# CPLD.net
KiCad netlist of a schematic drawn in Altium Designer
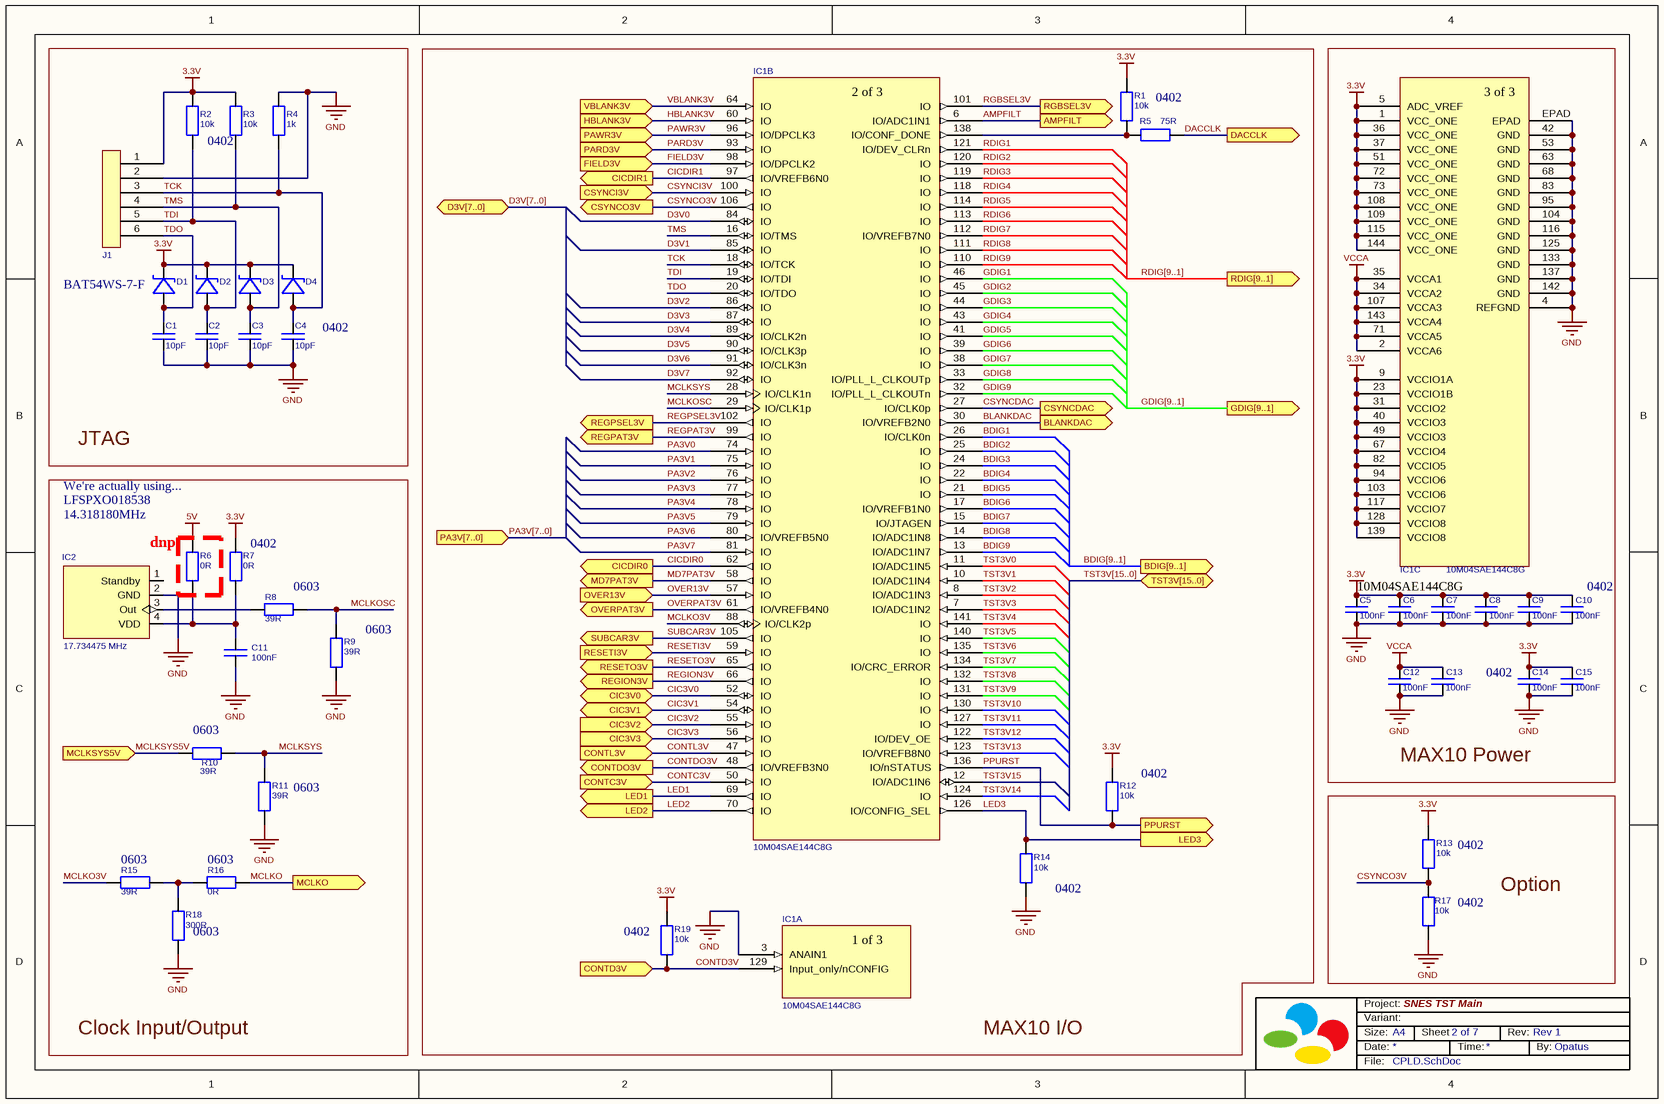
[diagram p0: CPLD.SchDoc]

(export (version "E")
  (design (tool "Eeschema 10.0.6"))
  (components
    (comp (ref "C1")
      (value "10pF")
      (footprint "Cap_0402_Chip")
      (fields
        (field (name "TOLERANCE") "±20%")
        (field (name "Comment") "Ceramic Capacitor 10pF 10V ±20% X7R 0402")
      )
      (libsource (lib "PCB") (part "Capacitor"))
    )
    (comp (ref "C2")
      (value "10pF")
      (footprint "Cap_0402_Chip")
      (fields
        (field (name "TOLERANCE") "±20%")
        (field (name "Comment") "Ceramic Capacitor 10pF 10V ±20% X7R 0402")
      )
      (libsource (lib "PCB") (part "Capacitor"))
    )
    (comp (ref "C3")
      (value "10pF")
      (footprint "Cap_0402_Chip")
      (fields
        (field (name "TOLERANCE") "±20%")
        (field (name "Comment") "Ceramic Capacitor 10pF 10V ±20% X7R 0402")
      )
      (libsource (lib "PCB") (part "Capacitor"))
    )
    (comp (ref "C4")
      (value "10pF")
      (footprint "Cap_0402_Chip")
      (fields
        (field (name "TOLERANCE") "±20%")
        (field (name "Comment") "Ceramic Capacitor 10pF 10V ±20% X7R 0402")
      )
      (libsource (lib "PCB") (part "Capacitor"))
    )
    (comp (ref "C5")
      (value "100nF")
      (footprint "Cap_0402_Chip")
      (fields
        (field (name "TOLERANCE") "±20%")
        (field (name "Comment") "Ceramic Capacitor 100nF 10V ±20% X7R 0402")
      )
      (libsource (lib "PCB") (part "Capacitor"))
    )
    (comp (ref "C6")
      (value "100nF")
      (footprint "Cap_0402_Chip")
      (fields
        (field (name "TOLERANCE") "±20%")
        (field (name "Comment") "Ceramic Capacitor 100nF 10V ±20% X7R 0402")
      )
      (libsource (lib "PCB") (part "Capacitor"))
    )
    (comp (ref "C7")
      (value "100nF")
      (footprint "Cap_0402_Chip")
      (fields
        (field (name "TOLERANCE") "±20%")
        (field (name "Comment") "Ceramic Capacitor 100nF 10V ±20% X7R 0402")
      )
      (libsource (lib "PCB") (part "Capacitor"))
    )
    (comp (ref "C8")
      (value "100nF")
      (footprint "Cap_0402_Chip")
      (fields
        (field (name "TOLERANCE") "±20%")
        (field (name "Comment") "Ceramic Capacitor 100nF 10V ±20% X7R 0402")
      )
      (libsource (lib "PCB") (part "Capacitor"))
    )
    (comp (ref "C9")
      (value "100nF")
      (footprint "Cap_0402_Chip")
      (fields
        (field (name "TOLERANCE") "±20%")
        (field (name "Comment") "Ceramic Capacitor 100nF 10V ±20% X7R 0402")
      )
      (libsource (lib "PCB") (part "Capacitor"))
    )
    (comp (ref "C10")
      (value "100nF")
      (footprint "Cap_0402_Chip")
      (fields
        (field (name "TOLERANCE") "±20%")
        (field (name "Comment") "Ceramic Capacitor 100nF 10V ±20% X7R 0402")
      )
      (libsource (lib "PCB") (part "Capacitor"))
    )
    (comp (ref "C11")
      (value "100nF")
      (footprint "Cap_0402_Chip")
      (fields
        (field (name "TOLERANCE") "±20%")
        (field (name "Comment") "Ceramic Capacitor 100nF 10V ±20% X7R 0402")
      )
      (libsource (lib "PCB") (part "Capacitor"))
    )
    (comp (ref "C12")
      (value "100nF")
      (footprint "Cap_0402_Chip")
      (fields
        (field (name "TOLERANCE") "±20%")
        (field (name "Comment") "Ceramic Capacitor 100nF 10V ±20% X7R 0402")
      )
      (libsource (lib "PCB") (part "Capacitor"))
    )
    (comp (ref "C13")
      (value "100nF")
      (footprint "Cap_0402_Chip")
      (fields
        (field (name "TOLERANCE") "±20%")
        (field (name "Comment") "Ceramic Capacitor 100nF 10V ±20% X7R 0402")
      )
      (libsource (lib "PCB") (part "Capacitor"))
    )
    (comp (ref "C14")
      (value "100nF")
      (footprint "Cap_0402_Chip")
      (fields
        (field (name "TOLERANCE") "±20%")
        (field (name "Comment") "Ceramic Capacitor 100nF 10V ±20% X7R 0402")
      )
      (libsource (lib "PCB") (part "Capacitor"))
    )
    (comp (ref "C15")
      (value "100nF")
      (footprint "Cap_0402_Chip")
      (fields
        (field (name "TOLERANCE") "±20%")
        (field (name "Comment") "Ceramic Capacitor 100nF 10V ±20% X7R 0402")
      )
      (libsource (lib "PCB") (part "Capacitor"))
    )
    (comp (ref "D1")
      (value "BAT54WS")
      (footprint "SOD323")
      (description "Schottky Diode")
      (fields (field (name "MANUFACTURER_PART_NUMBER") "BAT54WS-7-F") (field (name "MANUFACTURER") "Diodes"))
      (libsource (lib "PCB") (part "Schottky Diode"))
    )
    (comp (ref "D2")
      (value "BAT54WS")
      (footprint "SOD323")
      (description "Schottky Diode")
      (fields (field (name "MANUFACTURER_PART_NUMBER") "BAT54WS-7-F") (field (name "MANUFACTURER") "Diodes"))
      (libsource (lib "PCB") (part "Schottky Diode"))
    )
    (comp (ref "D3")
      (value "BAT54WS")
      (footprint "SOD323")
      (description "Schottky Diode")
      (fields (field (name "MANUFACTURER_PART_NUMBER") "BAT54WS-7-F") (field (name "MANUFACTURER") "Diodes"))
      (libsource (lib "PCB") (part "Schottky Diode"))
    )
    (comp (ref "D4")
      (value "BAT54WS")
      (footprint "SOD323")
      (description "Schottky Diode")
      (fields (field (name "MANUFACTURER_PART_NUMBER") "BAT54WS-7-F") (field (name "MANUFACTURER") "Diodes"))
      (libsource (lib "PCB") (part "Schottky Diode"))
    )
    (comp (ref "IC1")
      (value "10M04SAE144C8G")
      (footprint "EQFP-144_A:1P65_")
      (description "No Description Available")
      (fields
        (field (name "MANUFACTURER_PART_NUMBER") "10M04SAE144C8G")
        (field (name "MANUFACTURER") "Intel")
        (field (name "COPYRIGHT") "Copyright (C) 2018 Accelerated Designs. All rights reserved")
      )
      (libsource (lib "PCB") (part "10M08SAE144C8G"))
    )
    (comp (ref "IC2")
      (value "17.734475 MHz")
      (footprint "Quarz 7.5mm")
      (description "Oscillator")
      (fields
        (field (name "FREQUENCY") "17.734475 MHz")
        (field (name "MANUFACTURER") "IQD Frequency")
        (field (name "MANUFACTURER_PART_NUMBER") "LFSPXO020648Bulk")
      )
      (libsource (lib "PCB") (part "Oscillator"))
    )
    (comp (ref "J1")
      (value "Conn 6P")
      (footprint "Con6P")
      (description "6 Pole Connector")
      (libsource (lib "PCB") (part "Conn 6P"))
    )
    (comp (ref "R1")
      (value "10k")
      (footprint "Res_0402_Chip")
      (fields (field (name "TOLERANCE") "±1%") (field (name "Comment") "Resistor 10k 0402 ±1%"))
      (libsource (lib "PCB") (part "R"))
    )
    (comp (ref "R2")
      (value "10k")
      (footprint "Res_0402_Chip")
      (fields (field (name "TOLERANCE") "±1%") (field (name "Comment") "Resistor 10k 0402 ±1%"))
      (libsource (lib "PCB") (part "R"))
    )
    (comp (ref "R3")
      (value "10k")
      (footprint "Res_0402_Chip")
      (fields (field (name "TOLERANCE") "±1%") (field (name "Comment") "Resistor 10k 0402 ±1%"))
      (libsource (lib "PCB") (part "R"))
    )
    (comp (ref "R4")
      (value "1k")
      (footprint "Res_0402_Chip")
      (fields (field (name "TOLERANCE") "±1%") (field (name "Comment") "Resistor 1k 0402 ±1%"))
      (libsource (lib "") (part "R_3"))
    )
    (comp (ref "R5")
      (value "75R")
      (footprint "Res_0402_Chip")
      (fields (field (name "TOLERANCE") "±1%") (field (name "Comment") "Resistor 75R 0402 ±1%"))
      (libsource (lib "") (part "R_2"))
    )
    (comp (ref "R6")
      (value "0R")
      (footprint "Res_0402_Chip")
      (fields (field (name "Comment") "Resistor 0R 0402 "))
      (libsource (lib "PCB") (part "R"))
    )
    (comp (ref "R7")
      (value "0R")
      (footprint "Res_0402_Chip")
      (fields (field (name "Comment") "Resistor 0R 0402 "))
      (libsource (lib "PCB") (part "R"))
    )
    (comp (ref "R8")
      (value "39R")
      (footprint "Res_0603_Chip")
      (fields (field (name "TOLERANCE") "±1%") (field (name "Comment") "Resistor 39R 0603 ±1%"))
      (libsource (lib "") (part "R_1"))
    )
    (comp (ref "R9")
      (value "39R")
      (footprint "Res_0603_Chip")
      (fields (field (name "TOLERANCE") "±1%") (field (name "Comment") "Resistor 39R 0603 ±1%"))
      (libsource (lib "PCB") (part "R"))
    )
    (comp (ref "R10")
      (value "39R")
      (footprint "Res_0603_Chip")
      (fields (field (name "TOLERANCE") "±1%") (field (name "Comment") "Resistor 39R 0603 ±1%"))
      (libsource (lib "") (part "R_1"))
    )
    (comp (ref "R11")
      (value "39R")
      (footprint "Res_0603_Chip")
      (fields (field (name "TOLERANCE") "±1%") (field (name "Comment") "Resistor 39R 0603 ±1%"))
      (libsource (lib "PCB") (part "R"))
    )
    (comp (ref "R12")
      (value "10k")
      (footprint "Res_0402_Chip")
      (fields (field (name "TOLERANCE") "±1%") (field (name "Comment") "Resistor 10k 0402 ±1%"))
      (libsource (lib "PCB") (part "R"))
    )
    (comp (ref "R13")
      (value "10k")
      (footprint "Res_0402_Chip")
      (fields (field (name "TOLERANCE") "±1%") (field (name "Comment") "Resistor 10k 0402 ±1%"))
      (libsource (lib "PCB") (part "R"))
    )
    (comp (ref "R14")
      (value "10k")
      (footprint "Res_0402_Chip")
      (fields (field (name "TOLERANCE") "±1%") (field (name "Comment") "Resistor 10k 0402 ±1%"))
      (libsource (lib "") (part "R_3"))
    )
    (comp (ref "R15")
      (value "39R")
      (footprint "Res_0603_Chip")
      (fields (field (name "TOLERANCE") "±1%") (field (name "Comment") "Resistor 39R 0603 ±1%"))
      (libsource (lib "") (part "R_1"))
    )
    (comp (ref "R16")
      (value "0R")
      (footprint "Res_0603_Chip")
      (fields (field (name "Comment") "Resistor 0R 0603 "))
      (libsource (lib "") (part "R_1"))
    )
    (comp (ref "R17")
      (value "10k")
      (footprint "Res_0402_Chip")
      (fields (field (name "TOLERANCE") "±1%") (field (name "Comment") "Resistor 10k 0402 ±1%"))
      (libsource (lib "PCB") (part "R"))
    )
    (comp (ref "R18")
      (value "300R")
      (footprint "Res_0603_Chip")
      (fields (field (name "TOLERANCE") "±1%") (field (name "Comment") "Resistor 300R 0603 ±1%"))
      (libsource (lib "PCB") (part "R"))
    )
    (comp (ref "R19")
      (value "10k")
      (footprint "Res_0402_Chip")
      (fields (field (name "TOLERANCE") "±1%") (field (name "Comment") "Resistor 10k 0402 ±1%"))
      (libsource (lib "PCB") (part "R"))
    )
  )
  (nets
    (net (code "1") (name "/AMPFILT") (class "Default")
      (node (ref "IC1") (pin "6") (pinfunction "IO/ADC1IN1_6") (pintype "output"))
    )
    (net (code "2") (name "/BDIG1") (class "Default")
      (node (ref "IC1") (pin "26") (pinfunction "IO/CLK0n_26") (pintype "output"))
    )
    (net (code "3") (name "/BDIG2") (class "Default")
      (node (ref "IC1") (pin "25") (pinfunction "IO_25") (pintype "output"))
    )
    (net (code "4") (name "/BDIG3") (class "Default")
      (node (ref "IC1") (pin "24") (pinfunction "IO_24") (pintype "output"))
    )
    (net (code "5") (name "/BDIG4") (class "Default")
      (node (ref "IC1") (pin "22") (pinfunction "IO_22") (pintype "output"))
    )
    (net (code "6") (name "/BDIG5") (class "Default")
      (node (ref "IC1") (pin "21") (pinfunction "IO_21") (pintype "output"))
    )
    (net (code "7") (name "/BDIG6") (class "Default")
      (node (ref "IC1") (pin "17") (pinfunction "IO/VREFB1N0_17") (pintype "output"))
    )
    (net (code "8") (name "/BDIG7") (class "Default")
      (node (ref "IC1") (pin "15") (pinfunction "IO/JTAGEN_15") (pintype "output"))
    )
    (net (code "9") (name "/BDIG8") (class "Default")
      (node (ref "IC1") (pin "14") (pinfunction "IO/ADC1IN8_14") (pintype "output"))
    )
    (net (code "10") (name "/BDIG9") (class "Default")
      (node (ref "IC1") (pin "13") (pinfunction "IO/ADC1IN7_13") (pintype "output"))
    )
    (net (code "12") (name "/BLANKDAC") (class "Default")
      (node (ref "IC1") (pin "30") (pinfunction "IO/VREFB2N0_30") (pintype "output"))
    )
    (net (code "13") (name "/CIC3V0") (class "Default")
      (node (ref "IC1") (pin "52") (pinfunction "IO_52") (pintype "bidirectional"))
    )
    (net (code "14") (name "/CIC3V1") (class "Default")
      (node (ref "IC1") (pin "54") (pinfunction "IO_54") (pintype "bidirectional"))
    )
    (net (code "15") (name "/CIC3V2") (class "Default")
      (node (ref "IC1") (pin "55") (pinfunction "IO_55") (pintype "input"))
    )
    (net (code "16") (name "/CIC3V3") (class "Default")
      (node (ref "IC1") (pin "56") (pinfunction "IO_56") (pintype "input"))
    )
    (net (code "17") (name "/CICDIR0") (class "Default")
      (node (ref "IC1") (pin "62") (pinfunction "IO_62") (pintype "output"))
    )
    (net (code "18") (name "/CICDIR1") (class "Default")
      (node (ref "IC1") (pin "97") (pinfunction "IO/VREFB6N0_97") (pintype "output"))
    )
    (net (code "19") (name "/CONTC3V") (class "Default")
      (node (ref "IC1") (pin "50") (pinfunction "IO_50") (pintype "input"))
    )
    (net (code "20") (name "/CONTD3V") (class "Default")
      (node (ref "IC1") (pin "129") (pinfunction "Input_only/nCONFIG_129") (pintype "input"))
      (node (ref "R19") (pin "2") (pintype "passive"))
    )
    (net (code "21") (name "/CONTDO3V") (class "Default")
      (node (ref "IC1") (pin "48") (pinfunction "IO/VREFB3N0_48") (pintype "output"))
    )
    (net (code "22") (name "/CONTL3V") (class "Default")
      (node (ref "IC1") (pin "47") (pinfunction "IO_47") (pintype "input"))
    )
    (net (code "23") (name "/CSYNCDAC") (class "Default")
      (node (ref "IC1") (pin "27") (pinfunction "IO/CLK0p_27") (pintype "output"))
    )
    (net (code "24") (name "/CSYNCI3V") (class "Default")
      (node (ref "IC1") (pin "100") (pinfunction "IO_100") (pintype "input"))
    )
    (net (code "25") (name "/CSYNCO3V") (class "Default")
      (node (ref "IC1") (pin "106") (pinfunction "IO_106") (pintype "output"))
      (node (ref "R13") (pin "2") (pintype "passive"))
      (node (ref "R17") (pin "1") (pintype "passive"))
    )
    (net (code "26") (name "/D3V0") (class "Default")
      (node (ref "IC1") (pin "84") (pinfunction "IO_84") (pintype "bidirectional"))
    )
    (net (code "27") (name "/D3V1") (class "Default")
      (node (ref "IC1") (pin "85") (pinfunction "IO_85") (pintype "bidirectional"))
    )
    (net (code "28") (name "/D3V2") (class "Default")
      (node (ref "IC1") (pin "86") (pinfunction "IO_86") (pintype "bidirectional"))
    )
    (net (code "29") (name "/D3V3") (class "Default")
      (node (ref "IC1") (pin "87") (pinfunction "IO_87") (pintype "bidirectional"))
    )
    (net (code "30") (name "/D3V4") (class "Default")
      (node (ref "IC1") (pin "89") (pinfunction "IO/CLK2n_89") (pintype "bidirectional"))
    )
    (net (code "31") (name "/D3V5") (class "Default")
      (node (ref "IC1") (pin "90") (pinfunction "IO/CLK3p_90") (pintype "bidirectional"))
    )
    (net (code "32") (name "/D3V6") (class "Default")
      (node (ref "IC1") (pin "91") (pinfunction "IO/CLK3n_91") (pintype "bidirectional"))
    )
    (net (code "33") (name "/D3V7") (class "Default")
      (node (ref "IC1") (pin "92") (pinfunction "IO_92") (pintype "bidirectional"))
    )
    (net (code "35") (name "/DACCLK") (class "Default") (node (ref "R5") (pin "2") (pintype "passive")))
    (net (code "36") (name "/FIELD3V") (class "Default")
      (node (ref "IC1") (pin "98") (pinfunction "IO/DPCLK2_98") (pintype "input"))
    )
    (net (code "37") (name "/GDIG1") (class "Default")
      (node (ref "IC1") (pin "46") (pinfunction "IO_46") (pintype "output"))
    )
    (net (code "38") (name "/GDIG2") (class "Default")
      (node (ref "IC1") (pin "45") (pinfunction "IO_45") (pintype "output"))
    )
    (net (code "39") (name "/GDIG3") (class "Default")
      (node (ref "IC1") (pin "44") (pinfunction "IO_44") (pintype "output"))
    )
    (net (code "40") (name "/GDIG4") (class "Default")
      (node (ref "IC1") (pin "43") (pinfunction "IO_43") (pintype "output"))
    )
    (net (code "41") (name "/GDIG5") (class "Default")
      (node (ref "IC1") (pin "41") (pinfunction "IO_41") (pintype "output"))
    )
    (net (code "42") (name "/GDIG6") (class "Default")
      (node (ref "IC1") (pin "39") (pinfunction "IO_39") (pintype "output"))
    )
    (net (code "43") (name "/GDIG7") (class "Default")
      (node (ref "IC1") (pin "38") (pinfunction "IO_38") (pintype "output"))
    )
    (net (code "44") (name "/GDIG8") (class "Default")
      (node (ref "IC1") (pin "33") (pinfunction "IO/PLL_L_CLKOUTp_33") (pintype "output"))
    )
    (net (code "45") (name "/GDIG9") (class "Default")
      (node (ref "IC1") (pin "32") (pinfunction "IO/PLL_L_CLKOUTn_32") (pintype "output"))
    )
    (net (code "47") (name "/HBLANK3V") (class "Default")
      (node (ref "IC1") (pin "60") (pinfunction "IO_60") (pintype "input"))
    )
    (net (code "48") (name "/LED1") (class "Default")
      (node (ref "IC1") (pin "69") (pinfunction "IO_69") (pintype "output"))
    )
    (net (code "49") (name "/LED2") (class "Default")
      (node (ref "IC1") (pin "70") (pinfunction "IO_70") (pintype "output"))
    )
    (net (code "50") (name "/LED3") (class "Default")
      (node (ref "IC1") (pin "126") (pinfunction "IO/CONFIG_SEL_126") (pintype "output"))
      (node (ref "R14") (pin "2") (pintype "passive"))
    )
    (net (code "51") (name "/MCLKO") (class "Default") (node (ref "R16") (pin "1") (pintype "passive")))
    (net (code "52") (name "/MCLKO3V") (class "Default")
      (node (ref "IC1") (pin "88") (pinfunction "IO/CLK2p_88") (pintype "bidirectional"))
      (node (ref "R15") (pin "2") (pintype "passive"))
    )
    (net (code "53") (name "/MCLKOSC") (class "Default")
      (node (ref "IC1") (pin "29") (pinfunction "IO/CLK1p_29") (pintype "input"))
      (node (ref "R8") (pin "1") (pintype "passive"))
      (node (ref "R9") (pin "1") (pintype "passive"))
    )
    (net (code "54") (name "/MCLKSYS") (class "Default")
      (node (ref "IC1") (pin "28") (pinfunction "IO/CLK1n_28") (pintype "input"))
      (node (ref "R10") (pin "1") (pintype "passive"))
      (node (ref "R11") (pin "1") (pintype "passive"))
    )
    (net (code "55") (name "/MCLKSYS5V") (class "Default") (node (ref "R10") (pin "2") (pintype "passive")))
    (net (code "56") (name "/MD7PAT3V") (class "Default")
      (node (ref "IC1") (pin "58") (pinfunction "IO_58") (pintype "output"))
    )
    (net (code "57") (name "/OVER13V") (class "Default")
      (node (ref "IC1") (pin "57") (pinfunction "IO_57") (pintype "input"))
    )
    (net (code "58") (name "/OVERPAT3V") (class "Default")
      (node (ref "IC1") (pin "61") (pinfunction "IO/VREFB4N0_61") (pintype "output"))
    )
    (net (code "59") (name "/PA3V0") (class "Default")
      (node (ref "IC1") (pin "74") (pinfunction "IO_74") (pintype "input"))
    )
    (net (code "60") (name "/PA3V1") (class "Default")
      (node (ref "IC1") (pin "75") (pinfunction "IO_75") (pintype "input"))
    )
    (net (code "61") (name "/PA3V2") (class "Default")
      (node (ref "IC1") (pin "76") (pinfunction "IO_76") (pintype "input"))
    )
    (net (code "62") (name "/PA3V3") (class "Default")
      (node (ref "IC1") (pin "77") (pinfunction "IO_77") (pintype "input"))
    )
    (net (code "63") (name "/PA3V4") (class "Default")
      (node (ref "IC1") (pin "78") (pinfunction "IO_78") (pintype "input"))
    )
    (net (code "64") (name "/PA3V5") (class "Default")
      (node (ref "IC1") (pin "79") (pinfunction "IO_79") (pintype "input"))
    )
    (net (code "65") (name "/PA3V6") (class "Default")
      (node (ref "IC1") (pin "80") (pinfunction "IO/VREFB5N0_80") (pintype "input"))
    )
    (net (code "66") (name "/PA3V7") (class "Default")
      (node (ref "IC1") (pin "81") (pinfunction "IO_81") (pintype "input"))
    )
    (net (code "68") (name "/PARD3V") (class "Default")
      (node (ref "IC1") (pin "93") (pinfunction "IO_93") (pintype "input"))
    )
    (net (code "69") (name "/PAWR3V") (class "Default")
      (node (ref "IC1") (pin "96") (pinfunction "IO/DPCLK3_96") (pintype "input"))
    )
    (net (code "70") (name "/PPURST") (class "Default")
      (node (ref "IC1") (pin "136") (pinfunction "IO/nSTATUS_136") (pintype "output"))
      (node (ref "R12") (pin "2") (pintype "passive"))
    )
    (net (code "71") (name "/RDIG1") (class "Default")
      (node (ref "IC1") (pin "121") (pinfunction "IO/DEV_CLRn_121") (pintype "output"))
    )
    (net (code "72") (name "/RDIG2") (class "Default")
      (node (ref "IC1") (pin "120") (pinfunction "IO_120") (pintype "output"))
    )
    (net (code "73") (name "/RDIG3") (class "Default")
      (node (ref "IC1") (pin "119") (pinfunction "IO_119") (pintype "output"))
    )
    (net (code "74") (name "/RDIG4") (class "Default")
      (node (ref "IC1") (pin "118") (pinfunction "IO_118") (pintype "output"))
    )
    (net (code "75") (name "/RDIG5") (class "Default")
      (node (ref "IC1") (pin "114") (pinfunction "IO_114") (pintype "output"))
    )
    (net (code "76") (name "/RDIG6") (class "Default")
      (node (ref "IC1") (pin "113") (pinfunction "IO_113") (pintype "output"))
    )
    (net (code "77") (name "/RDIG7") (class "Default")
      (node (ref "IC1") (pin "112") (pinfunction "IO/VREFB7N0_112") (pintype "output"))
    )
    (net (code "78") (name "/RDIG8") (class "Default")
      (node (ref "IC1") (pin "111") (pinfunction "IO_111") (pintype "output"))
    )
    (net (code "79") (name "/RDIG9") (class "Default")
      (node (ref "IC1") (pin "110") (pinfunction "IO_110") (pintype "output"))
    )
    (net (code "81") (name "/REGION3V") (class "Default")
      (node (ref "IC1") (pin "66") (pinfunction "IO_66") (pintype "output"))
    )
    (net (code "82") (name "/REGPAT3V") (class "Default")
      (node (ref "IC1") (pin "99") (pinfunction "IO_99") (pintype "output"))
    )
    (net (code "83") (name "/REGPSEL3V") (class "Default")
      (node (ref "IC1") (pin "102") (pinfunction "IO_102") (pintype "output"))
    )
    (net (code "84") (name "/RESETI3V") (class "Default")
      (node (ref "IC1") (pin "59") (pinfunction "IO_59") (pintype "input"))
    )
    (net (code "85") (name "/RESETO3V") (class "Default")
      (node (ref "IC1") (pin "65") (pinfunction "IO_65") (pintype "output"))
    )
    (net (code "86") (name "/RGBSEL3V") (class "Default")
      (node (ref "IC1") (pin "101") (pinfunction "IO_101") (pintype "output"))
    )
    (net (code "87") (name "/SUBCAR3V") (class "Default")
      (node (ref "IC1") (pin "105") (pinfunction "IO_105") (pintype "output"))
    )
    (net (code "88") (name "/TCK") (class "Default")
      (node (ref "C4") (pin "1") (pintype "passive"))
      (node (ref "D4") (pin "2") (pinfunction "A_2") (pintype "passive"))
      (node (ref "IC1") (pin "18") (pinfunction "IO/TCK_18") (pintype "bidirectional"))
      (node (ref "J1") (pin "3") (pintype "passive"))
      (node (ref "R4") (pin "1") (pintype "passive"))
    )
    (net (code "89") (name "/TDI") (class "Default")
      (node (ref "C2") (pin "1") (pintype "passive"))
      (node (ref "D2") (pin "2") (pinfunction "A_2") (pintype "passive"))
      (node (ref "IC1") (pin "19") (pinfunction "IO/TDI_19") (pintype "bidirectional"))
      (node (ref "J1") (pin "5") (pintype "passive"))
      (node (ref "R2") (pin "2") (pintype "passive"))
    )
    (net (code "90") (name "/TDO") (class "Default")
      (node (ref "C1") (pin "1") (pintype "passive"))
      (node (ref "D1") (pin "2") (pinfunction "A_2") (pintype "passive"))
      (node (ref "IC1") (pin "20") (pinfunction "IO/TDO_20") (pintype "bidirectional"))
      (node (ref "J1") (pin "6") (pintype "passive"))
    )
    (net (code "91") (name "/TMS") (class "Default")
      (node (ref "C3") (pin "1") (pintype "passive"))
      (node (ref "D3") (pin "2") (pinfunction "A_2") (pintype "passive"))
      (node (ref "IC1") (pin "16") (pinfunction "IO/TMS_16") (pintype "bidirectional"))
      (node (ref "J1") (pin "4") (pintype "passive"))
      (node (ref "R3") (pin "2") (pintype "passive"))
    )
    (net (code "92") (name "/TST3V0") (class "Default")
      (node (ref "IC1") (pin "11") (pinfunction "IO/ADC1IN5_11") (pintype "input"))
    )
    (net (code "93") (name "/TST3V1") (class "Default")
      (node (ref "IC1") (pin "10") (pinfunction "IO/ADC1IN4_10") (pintype "input"))
    )
    (net (code "94") (name "/TST3V2") (class "Default")
      (node (ref "IC1") (pin "8") (pinfunction "IO/ADC1IN3_8") (pintype "input"))
    )
    (net (code "95") (name "/TST3V3") (class "Default")
      (node (ref "IC1") (pin "7") (pinfunction "IO/ADC1IN2_7") (pintype "input"))
    )
    (net (code "96") (name "/TST3V4") (class "Default")
      (node (ref "IC1") (pin "141") (pinfunction "IO_141") (pintype "input"))
    )
    (net (code "97") (name "/TST3V5") (class "Default")
      (node (ref "IC1") (pin "140") (pinfunction "IO_140") (pintype "input"))
    )
    (net (code "98") (name "/TST3V6") (class "Default")
      (node (ref "IC1") (pin "135") (pinfunction "IO_135") (pintype "input"))
    )
    (net (code "99") (name "/TST3V7") (class "Default")
      (node (ref "IC1") (pin "134") (pinfunction "IO/CRC_ERROR_134") (pintype "input"))
    )
    (net (code "100") (name "/TST3V8") (class "Default")
      (node (ref "IC1") (pin "132") (pinfunction "IO_132") (pintype "input"))
    )
    (net (code "101") (name "/TST3V9") (class "Default")
      (node (ref "IC1") (pin "131") (pinfunction "IO_131") (pintype "input"))
    )
    (net (code "102") (name "/TST3V10") (class "Default")
      (node (ref "IC1") (pin "130") (pinfunction "IO_130") (pintype "input"))
    )
    (net (code "103") (name "/TST3V11") (class "Default")
      (node (ref "IC1") (pin "127") (pinfunction "IO_127") (pintype "input"))
    )
    (net (code "104") (name "/TST3V12") (class "Default")
      (node (ref "IC1") (pin "122") (pinfunction "IO/DEV_OE_122") (pintype "input"))
    )
    (net (code "105") (name "/TST3V13") (class "Default")
      (node (ref "IC1") (pin "123") (pinfunction "IO/VREFB8N0_123") (pintype "input"))
    )
    (net (code "106") (name "/TST3V14") (class "Default")
      (node (ref "IC1") (pin "124") (pinfunction "IO_124") (pintype "input"))
    )
    (net (code "107") (name "/TST3V15") (class "Default")
      (node (ref "IC1") (pin "12") (pinfunction "IO/ADC1IN6_12") (pintype "bidirectional"))
    )
    (net (code "109") (name "/VBLANK3V") (class "Default")
      (node (ref "IC1") (pin "64") (pinfunction "IO_64") (pintype "input"))
    )
    (net (code "110") (name "3.3V") (class "Default")
      (node (ref "C10") (pin "1") (pintype "passive"))
      (node (ref "C14") (pin "1") (pintype "passive"))
      (node (ref "C15") (pin "1") (pintype "passive"))
      (node (ref "C5") (pin "1") (pintype "passive"))
      (node (ref "C6") (pin "1") (pintype "passive"))
      (node (ref "C7") (pin "1") (pintype "passive"))
      (node (ref "C8") (pin "1") (pintype "passive"))
      (node (ref "C9") (pin "1") (pintype "passive"))
      (node (ref "D1") (pin "1") (pinfunction "K_1") (pintype "passive"))
      (node (ref "D2") (pin "1") (pinfunction "K_1") (pintype "passive"))
      (node (ref "D3") (pin "1") (pinfunction "K_1") (pintype "passive"))
      (node (ref "D4") (pin "1") (pinfunction "K_1") (pintype "passive"))
      (node (ref "IC1") (pin "1") (pinfunction "VCC_ONE_1") (pintype "power_in"))
      (node (ref "IC1") (pin "103") (pinfunction "VCCIO6_103") (pintype "power_in"))
      (node (ref "IC1") (pin "108") (pinfunction "VCC_ONE_108") (pintype "power_in"))
      (node (ref "IC1") (pin "109") (pinfunction "VCC_ONE_109") (pintype "power_in"))
      (node (ref "IC1") (pin "115") (pinfunction "VCC_ONE_115") (pintype "power_in"))
      (node (ref "IC1") (pin "117") (pinfunction "VCCIO7_117") (pintype "power_in"))
      (node (ref "IC1") (pin "128") (pinfunction "VCCIO8_128") (pintype "power_in"))
      (node (ref "IC1") (pin "139") (pinfunction "VCCIO8_139") (pintype "power_in"))
      (node (ref "IC1") (pin "144") (pinfunction "VCC_ONE_144") (pintype "power_in"))
      (node (ref "IC1") (pin "23") (pinfunction "VCCIO1B_23") (pintype "power_in"))
      (node (ref "IC1") (pin "31") (pinfunction "VCCIO2_31") (pintype "power_in"))
      (node (ref "IC1") (pin "36") (pinfunction "VCC_ONE_36") (pintype "power_in"))
      (node (ref "IC1") (pin "37") (pinfunction "VCC_ONE_37") (pintype "power_in"))
      (node (ref "IC1") (pin "40") (pinfunction "VCCIO3_40") (pintype "power_in"))
      (node (ref "IC1") (pin "49") (pinfunction "VCCIO3_49") (pintype "power_in"))
      (node (ref "IC1") (pin "5") (pinfunction "ADC_VREF_5") (pintype "power_in"))
      (node (ref "IC1") (pin "51") (pinfunction "VCC_ONE_51") (pintype "power_in"))
      (node (ref "IC1") (pin "67") (pinfunction "VCCIO4_67") (pintype "power_in"))
      (node (ref "IC1") (pin "72") (pinfunction "VCC_ONE_72") (pintype "power_in"))
      (node (ref "IC1") (pin "73") (pinfunction "VCC_ONE_73") (pintype "power_in"))
      (node (ref "IC1") (pin "82") (pinfunction "VCCIO5_82") (pintype "power_in"))
      (node (ref "IC1") (pin "9") (pinfunction "VCCIO1A_9") (pintype "power_in"))
      (node (ref "IC1") (pin "94") (pinfunction "VCCIO6_94") (pintype "power_in"))
      (node (ref "J1") (pin "1") (pintype "passive"))
      (node (ref "R1") (pin "1") (pintype "passive"))
      (node (ref "R12") (pin "1") (pintype "passive"))
      (node (ref "R13") (pin "1") (pintype "passive"))
      (node (ref "R19") (pin "1") (pintype "passive"))
      (node (ref "R2") (pin "1") (pintype "passive"))
      (node (ref "R3") (pin "1") (pintype "passive"))
      (node (ref "R7") (pin "1") (pintype "passive"))
    )
    (net (code "111") (name "5V") (class "Default") (node (ref "R6") (pin "1") (pintype "passive")))
    (net (code "112") (name "GND") (class "Default")
      (node (ref "C1") (pin "2") (pintype "passive"))
      (node (ref "C10") (pin "2") (pintype "passive"))
      (node (ref "C11") (pin "2") (pintype "passive"))
      (node (ref "C12") (pin "2") (pintype "passive"))
      (node (ref "C13") (pin "2") (pintype "passive"))
      (node (ref "C14") (pin "2") (pintype "passive"))
      (node (ref "C15") (pin "2") (pintype "passive"))
      (node (ref "C2") (pin "2") (pintype "passive"))
      (node (ref "C3") (pin "2") (pintype "passive"))
      (node (ref "C4") (pin "2") (pintype "passive"))
      (node (ref "C5") (pin "2") (pintype "passive"))
      (node (ref "C6") (pin "2") (pintype "passive"))
      (node (ref "C7") (pin "2") (pintype "passive"))
      (node (ref "C8") (pin "2") (pintype "passive"))
      (node (ref "C9") (pin "2") (pintype "passive"))
      (node (ref "IC1") (pin "104") (pinfunction "GND_104") (pintype "power_in"))
      (node (ref "IC1") (pin "116") (pinfunction "GND_116") (pintype "power_in"))
      (node (ref "IC1") (pin "125") (pinfunction "GND_125") (pintype "power_in"))
      (node (ref "IC1") (pin "133") (pinfunction "GND_133") (pintype "power_in"))
      (node (ref "IC1") (pin "137") (pinfunction "GND_137") (pintype "power_in"))
      (node (ref "IC1") (pin "142") (pinfunction "GND_142") (pintype "power_in"))
      (node (ref "IC1") (pin "3") (pinfunction "ANAIN1_3") (pintype "input"))
      (node (ref "IC1") (pin "4") (pinfunction "REFGND_4") (pintype "power_in"))
      (node (ref "IC1") (pin "42") (pinfunction "GND_42") (pintype "power_in"))
      (node (ref "IC1") (pin "53") (pinfunction "GND_53") (pintype "power_in"))
      (node (ref "IC1") (pin "63") (pinfunction "GND_63") (pintype "power_in"))
      (node (ref "IC1") (pin "68") (pinfunction "GND_68") (pintype "power_in"))
      (node (ref "IC1") (pin "83") (pinfunction "GND_83") (pintype "power_in"))
      (node (ref "IC1") (pin "95") (pinfunction "GND_95") (pintype "power_in"))
      (node (ref "IC1") (pin "EPAD") (pinfunction "EPAD_EPAD") (pintype "power_in"))
      (node (ref "IC2") (pin "2") (pinfunction "GND_2") (pintype "passive"))
      (node (ref "J1") (pin "2") (pintype "passive"))
      (node (ref "R11") (pin "2") (pintype "passive"))
      (node (ref "R14") (pin "1") (pintype "passive"))
      (node (ref "R17") (pin "2") (pintype "passive"))
      (node (ref "R18") (pin "2") (pintype "passive"))
      (node (ref "R4") (pin "2") (pintype "passive"))
      (node (ref "R9") (pin "2") (pintype "passive"))
    )
    (net (code "113") (name "Net-(IC1B-IO{slash}CONF_DONE)") (class "Default")
      (node (ref "IC1") (pin "138") (pinfunction "IO/CONF_DONE_138") (pintype "output"))
      (node (ref "R1") (pin "2") (pintype "passive"))
      (node (ref "R5") (pin "1") (pintype "passive"))
    )
    (net (code "114") (name "Net-(IC2-Out)") (class "Default")
      (node (ref "IC2") (pin "3") (pinfunction "Out_3") (pintype "output"))
      (node (ref "R8") (pin "2") (pintype "passive"))
    )
    (net (code "115") (name "Net-(IC2-VDD)") (class "Default")
      (node (ref "C11") (pin "1") (pintype "passive"))
      (node (ref "IC2") (pin "4") (pinfunction "VDD_4") (pintype "passive"))
      (node (ref "R6") (pin "2") (pintype "passive"))
      (node (ref "R7") (pin "2") (pintype "passive"))
    )
    (net (code "116") (name "Net-(R15-Pad1)") (class "Default")
      (node (ref "R15") (pin "1") (pintype "passive"))
      (node (ref "R16") (pin "2") (pintype "passive"))
      (node (ref "R18") (pin "1") (pintype "passive"))
    )
    (net (code "117") (name "VCCA") (class "Default")
      (node (ref "C12") (pin "1") (pintype "passive"))
      (node (ref "C13") (pin "1") (pintype "passive"))
      (node (ref "IC1") (pin "107") (pinfunction "VCCA3_107") (pintype "power_in"))
      (node (ref "IC1") (pin "143") (pinfunction "VCCA4_143") (pintype "power_in"))
      (node (ref "IC1") (pin "2") (pinfunction "VCCA6_2") (pintype "power_in"))
      (node (ref "IC1") (pin "34") (pinfunction "VCCA2_34") (pintype "power_in"))
      (node (ref "IC1") (pin "35") (pinfunction "VCCA1_35") (pintype "power_in"))
      (node (ref "IC1") (pin "71") (pinfunction "VCCA5_71") (pintype "power_in"))
    )
    (net (code "118") (name "unconnected-(IC2-Standby-Pad1)") (class "Default")
      (node (ref "IC2") (pin "1") (pinfunction "Standby_1") (pintype "passive"))
    )
  )
)
